# heater.net
KiCad netlist of a schematic drawn in Altium Designer
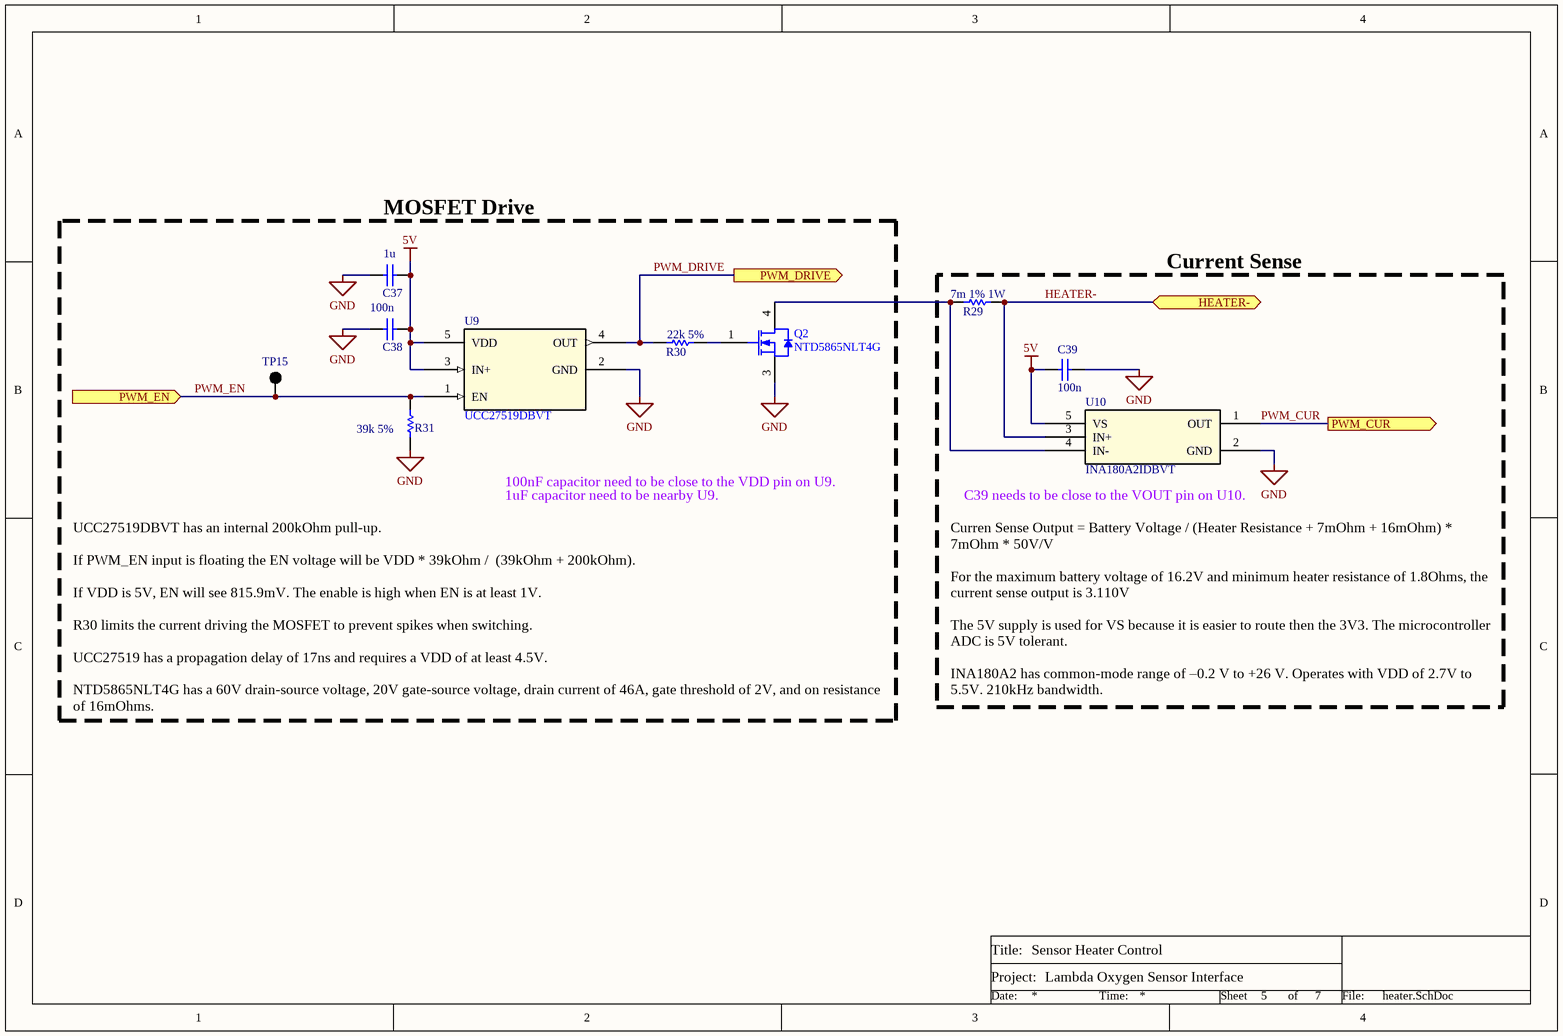
[diagram p0: heater.SchDoc]

(export (version "E")
  (design (tool "Eeschema 10.0.6"))
  (components
    (comp (ref "C37")
      (value "1u")
      (footprint "1206")
      (description "Generic 1206 Capacitor")
      (libsource (lib "symbol_library") (part "C_1206"))
    )
    (comp (ref "C38")
      (value "100n")
      (footprint "0805")
      (description "Generic 0805 Capacitor")
      (libsource (lib "symbol_library") (part "C_0805"))
    )
    (comp (ref "C39")
      (value "100n")
      (footprint "0805")
      (description "Generic 0805 Capacitor")
      (libsource (lib "symbol_library") (part "C_0805"))
    )
    (comp (ref "Q2")
      (value "NTD5865NLT4G")
      (footprint "TO-252AA")
      (description "N-Channel 60V 46A (Tc) 71W (Tc) Surface Mount DPAK")
      (libsource (lib "symbol_library") (part "NTD5865NL"))
    )
    (comp (ref "R29")
      (value "7m 1% 1W")
      (footprint "1206")
      (description "Generic 1206 Resistor")
      (libsource (lib "symbol_library") (part "R_1206"))
    )
    (comp (ref "R30")
      (value "22k 5%")
      (footprint "0603")
      (description "Generic 0603 Resistor")
      (libsource (lib "symbol_library") (part "R_0603"))
    )
    (comp (ref "R31")
      (value "39k 5%")
      (footprint "0603")
      (description "Generic 0603 Resistor")
      (libsource (lib "symbol_library") (part "R_0603"))
    )
    (comp (ref "TP15")
      (value "5001")
      (footprint "KSTN-5001")
      (description "Test Point, Black, 1-Pin THD, RoHS, Bulk")
      (fields (field (name "MANUFACTURER") "Keystone"))
      (libsource (lib "symbol_library") (part "TP5001"))
    )
    (comp (ref "U9")
      (value "UCC27519DBVT")
      (footprint "DDC0005A_M")
      (description "Low-Side Gate Driver IC Non-Inverting SOT-23-5")
      (libsource (lib "symbol_library") (part "UCC27519"))
    )
    (comp (ref "U10")
      (value "INA180A2IDBVT")
      (footprint "DDC0005A_M")
      (description "Current Sense Amplifier 1 Circuit Rail-to-Rail SOT-23-5")
      (libsource (lib "symbol_library") (part "INA180A2"))
    )
  )
  (nets
    (net (code "1") (name "/HEATER-") (class "Default")
      (node (ref "R29") (pin "2") (pinfunction "2_2") (pintype "passive"))
      (node (ref "U10") (pin "3") (pinfunction "IN+_3") (pintype "passive"))
    )
    (net (code "2") (name "/PWM_CUR") (class "Default")
      (node (ref "U10") (pin "1") (pinfunction "OUT_1") (pintype "passive"))
    )
    (net (code "3") (name "/PWM_DRIVE") (class "Default")
      (node (ref "R30") (pin "1") (pinfunction "1_1") (pintype "passive"))
      (node (ref "U9") (pin "4") (pinfunction "OUT_4") (pintype "output"))
    )
    (net (code "4") (name "/PWM_EN") (class "Default")
      (node (ref "R31") (pin "2") (pinfunction "2_2") (pintype "passive"))
      (node (ref "TP15") (pin "1") (pintype "passive"))
      (node (ref "U9") (pin "1") (pinfunction "EN_1") (pintype "input"))
    )
    (net (code "5") (name "5V") (class "Default")
      (node (ref "C37") (pin "2") (pinfunction "2_2") (pintype "passive"))
      (node (ref "C38") (pin "2") (pinfunction "2_2") (pintype "passive"))
      (node (ref "C39") (pin "2") (pinfunction "2_2") (pintype "passive"))
      (node (ref "U10") (pin "5") (pinfunction "VS_5") (pintype "power_in"))
      (node (ref "U9") (pin "3") (pinfunction "IN+_3") (pintype "input"))
      (node (ref "U9") (pin "5") (pinfunction "VDD_5") (pintype "power_in"))
    )
    (net (code "6") (name "GND") (class "Default")
      (node (ref "C37") (pin "1") (pinfunction "1_1") (pintype "passive"))
      (node (ref "C38") (pin "1") (pinfunction "1_1") (pintype "passive"))
      (node (ref "C39") (pin "1") (pinfunction "1_1") (pintype "passive"))
      (node (ref "Q2") (pin "3") (pinfunction "S_3") (pintype "passive"))
      (node (ref "R31") (pin "1") (pinfunction "1_1") (pintype "passive"))
      (node (ref "U10") (pin "2") (pinfunction "GND_2") (pintype "power_in"))
      (node (ref "U9") (pin "2") (pinfunction "GND_2") (pintype "power_in"))
    )
    (net (code "7") (name "Net-(Q2-D)") (class "Default")
      (node (ref "Q2") (pin "4") (pinfunction "D_4") (pintype "passive"))
      (node (ref "R29") (pin "1") (pinfunction "1_1") (pintype "passive"))
      (node (ref "U10") (pin "4") (pinfunction "IN-_4") (pintype "passive"))
    )
    (net (code "8") (name "Net-(Q2-G)") (class "Default")
      (node (ref "Q2") (pin "1") (pinfunction "G_1") (pintype "passive"))
      (node (ref "R30") (pin "2") (pinfunction "2_2") (pintype "passive"))
    )
  )
)
